# receiver.net
KiCad netlist of a schematic drawn in EAGLE
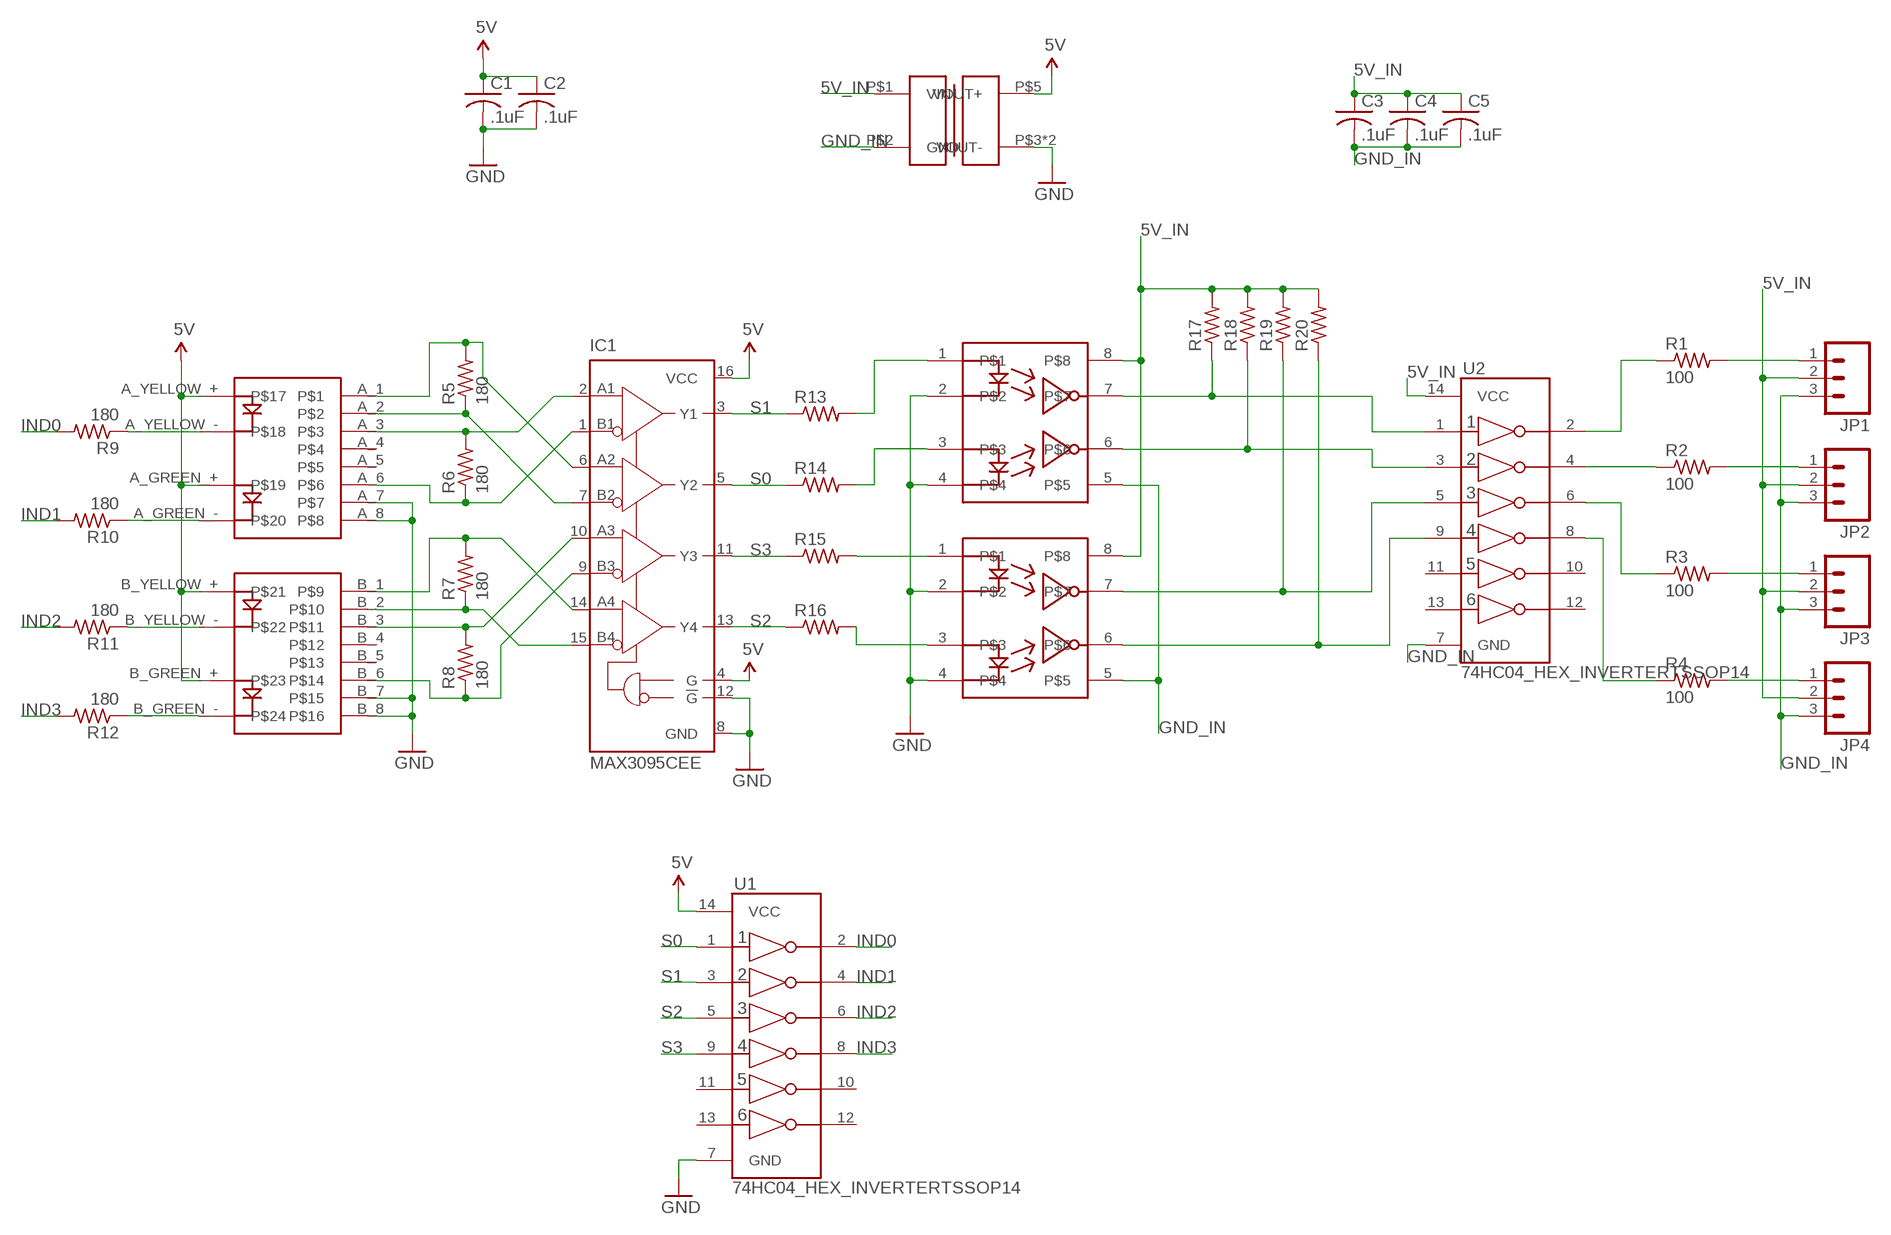
[diagram p0: schematic, sheet 1]

(export (version "E")
  (design (tool "Eeschema 10.0.6"))
  (components
    (comp (ref "C1")
      (value ".1uF")
      (footprint "eagle-import:C0603")
      (libsource (lib "eagle-import") (part "C-USC0603"))
    )
    (comp (ref "C2")
      (value ".1uF")
      (footprint "eagle-import:C0603")
      (libsource (lib "eagle-import") (part "C-USC0603"))
    )
    (comp (ref "C3")
      (value ".1uF")
      (footprint "eagle-import:C0603")
      (libsource (lib "eagle-import") (part "C-USC0603"))
    )
    (comp (ref "C4")
      (value ".1uF")
      (footprint "eagle-import:C0603")
      (libsource (lib "eagle-import") (part "C-USC0603"))
    )
    (comp (ref "C5")
      (value ".1uF")
      (footprint "eagle-import:C0603")
      (libsource (lib "eagle-import") (part "C-USC0603"))
    )
    (comp (ref "IC1")
      (value "MAX3095CEE")
      (footprint "eagle-import:QSOP16")
      (fields (field (name "MPN") "MAX3095CEE+"))
      (libsource (lib "eagle-import") (part "MAX309EE5C"))
    )
    (comp (ref "JP1")
      (value "M03-SCREW-5MM")
      (footprint "eagle-import:SCREWTERMINAL-5MM-3")
      (libsource (lib "eagle-import") (part "M03-SCREW-5MM"))
    )
    (comp (ref "JP2")
      (value "M03-SCREW-5MM")
      (footprint "eagle-import:SCREWTERMINAL-5MM-3")
      (libsource (lib "eagle-import") (part "M03-SCREW-5MM"))
    )
    (comp (ref "JP3")
      (value "M03-SCREW-5MM")
      (footprint "eagle-import:SCREWTERMINAL-5MM-3")
      (libsource (lib "eagle-import") (part "M03-SCREW-5MM"))
    )
    (comp (ref "JP4")
      (value "M03-SCREW-5MM")
      (footprint "eagle-import:SCREWTERMINAL-5MM-3")
      (libsource (lib "eagle-import") (part "M03-SCREW-5MM"))
    )
    (comp (ref "R1")
      (value "100")
      (footprint "eagle-import:R0603")
      (libsource (lib "eagle-import") (part "R-US_R0603"))
    )
    (comp (ref "R2")
      (value "100")
      (footprint "eagle-import:R0603")
      (libsource (lib "eagle-import") (part "R-US_R0603"))
    )
    (comp (ref "R3")
      (value "100")
      (footprint "eagle-import:R0603")
      (libsource (lib "eagle-import") (part "R-US_R0603"))
    )
    (comp (ref "R4")
      (value "100")
      (footprint "eagle-import:R0603")
      (libsource (lib "eagle-import") (part "R-US_R0603"))
    )
    (comp (ref "R5")
      (value "180")
      (footprint "eagle-import:R0603")
      (libsource (lib "eagle-import") (part "R-US_R0603"))
    )
    (comp (ref "R6")
      (value "180")
      (footprint "eagle-import:R0603")
      (libsource (lib "eagle-import") (part "R-US_R0603"))
    )
    (comp (ref "R7")
      (value "180")
      (footprint "eagle-import:R0603")
      (libsource (lib "eagle-import") (part "R-US_R0603"))
    )
    (comp (ref "R8")
      (value "180")
      (footprint "eagle-import:R0603")
      (libsource (lib "eagle-import") (part "R-US_R0603"))
    )
    (comp (ref "R9")
      (value "180")
      (footprint "eagle-import:R0603")
      (libsource (lib "eagle-import") (part "R-US_R0603"))
    )
    (comp (ref "R10")
      (value "180")
      (footprint "eagle-import:R0603")
      (libsource (lib "eagle-import") (part "R-US_R0603"))
    )
    (comp (ref "R11")
      (value "180")
      (footprint "eagle-import:R0603")
      (libsource (lib "eagle-import") (part "R-US_R0603"))
    )
    (comp (ref "R12")
      (value "180")
      (footprint "eagle-import:R0603")
      (libsource (lib "eagle-import") (part "R-US_R0603"))
    )
    (comp (ref "R13")
      (value "R-US_R0603")
      (footprint "eagle-import:R0603")
      (libsource (lib "eagle-import") (part "R-US_R0603"))
    )
    (comp (ref "R14")
      (value "R-US_R0603")
      (footprint "eagle-import:R0603")
      (libsource (lib "eagle-import") (part "R-US_R0603"))
    )
    (comp (ref "R15")
      (value "R-US_R0603")
      (footprint "eagle-import:R0603")
      (libsource (lib "eagle-import") (part "R-US_R0603"))
    )
    (comp (ref "R16")
      (value "R-US_R0603")
      (footprint "eagle-import:R0603")
      (libsource (lib "eagle-import") (part "R-US_R0603"))
    )
    (comp (ref "R17")
      (value "R-US_R0603")
      (footprint "eagle-import:R0603")
      (libsource (lib "eagle-import") (part "R-US_R0603"))
    )
    (comp (ref "R18")
      (value "R-US_R0603")
      (footprint "eagle-import:R0603")
      (libsource (lib "eagle-import") (part "R-US_R0603"))
    )
    (comp (ref "R19")
      (value "R-US_R0603")
      (footprint "eagle-import:R0603")
      (libsource (lib "eagle-import") (part "R-US_R0603"))
    )
    (comp (ref "R20")
      (value "R-US_R0603")
      (footprint "eagle-import:R0603")
      (libsource (lib "eagle-import") (part "R-US_R0603"))
    )
    (comp (ref "U$1")
      (value "RJ45_2X1")
      (footprint "eagle-import:RJ45_2X1")
      (libsource (lib "eagle-import") (part "RJ45_2X1"))
    )
    (comp (ref "U$2")
      (value "DC_DC_ISOLATED_0505")
      (footprint "eagle-import:IB_XLS-1W")
      (libsource (lib "eagle-import") (part "DC_DC_ISOLATED_0505"))
    )
    (comp (ref "U$3")
      (value "HCPL-0631-500E")
      (footprint "eagle-import:SO08")
      (libsource (lib "eagle-import") (part "HCPL-0631-500E"))
    )
    (comp (ref "U$4")
      (value "HCPL-0631-500E")
      (footprint "eagle-import:SO08")
      (libsource (lib "eagle-import") (part "HCPL-0631-500E"))
    )
    (comp (ref "U1")
      (value "74HC04_HEX_INVERTERTSSOP14")
      (footprint "eagle-import:TSSOP14")
      (libsource (lib "eagle-import") (part "74HC04_HEX_INVERTERTSSOP14"))
    )
    (comp (ref "U2")
      (value "74HC04_HEX_INVERTERTSSOP14")
      (footprint "eagle-import:TSSOP14")
      (libsource (lib "eagle-import") (part "74HC04_HEX_INVERTERTSSOP14"))
    )
  )
  (nets
    (net (code "1") (name "/5V_IN") (class "Default")
      (node (ref "C3") (pin "1") (pinfunction "1_1") (pintype "passive"))
      (node (ref "C4") (pin "1") (pinfunction "1_1") (pintype "passive"))
      (node (ref "C5") (pin "1") (pinfunction "1_1") (pintype "passive"))
      (node (ref "JP1") (pin "2") (pinfunction "2_2") (pintype "passive"))
      (node (ref "JP2") (pin "2") (pinfunction "2_2") (pintype "passive"))
      (node (ref "JP3") (pin "2") (pinfunction "2_2") (pintype "passive"))
      (node (ref "JP4") (pin "2") (pinfunction "2_2") (pintype "passive"))
      (node (ref "R17") (pin "2") (pinfunction "2_2") (pintype "passive"))
      (node (ref "R18") (pin "2") (pinfunction "2_2") (pintype "passive"))
      (node (ref "R19") (pin "2") (pinfunction "2_2") (pintype "passive"))
      (node (ref "R20") (pin "2") (pinfunction "2_2") (pintype "passive"))
      (node (ref "U$2") (pin "P$1") (pinfunction "VIN_P$1") (pintype "power_in"))
      (node (ref "U$3") (pin "8") (pinfunction "P$8_8") (pintype "bidirectional"))
      (node (ref "U$4") (pin "8") (pinfunction "P$8_8") (pintype "bidirectional"))
      (node (ref "U2") (pin "14") (pinfunction "VCC_14") (pintype "power_in"))
    )
    (net (code "2") (name "/GND_IN") (class "Default")
      (node (ref "C3") (pin "2") (pinfunction "2_2") (pintype "passive"))
      (node (ref "C4") (pin "2") (pinfunction "2_2") (pintype "passive"))
      (node (ref "C5") (pin "2") (pinfunction "2_2") (pintype "passive"))
      (node (ref "JP1") (pin "3") (pinfunction "3_3") (pintype "passive"))
      (node (ref "JP2") (pin "3") (pinfunction "3_3") (pintype "passive"))
      (node (ref "JP3") (pin "3") (pinfunction "3_3") (pintype "passive"))
      (node (ref "JP4") (pin "3") (pinfunction "3_3") (pintype "passive"))
      (node (ref "U$2") (pin "P$2") (pinfunction "GND_P$2") (pintype "power_in"))
      (node (ref "U$3") (pin "5") (pinfunction "P$5_5") (pintype "bidirectional"))
      (node (ref "U$4") (pin "5") (pinfunction "P$5_5") (pintype "bidirectional"))
      (node (ref "U2") (pin "7") (pinfunction "GND_7") (pintype "power_in"))
    )
    (net (code "3") (name "/IND0") (class "Default")
      (node (ref "R9") (pin "2") (pinfunction "2_2") (pintype "passive"))
      (node (ref "U1") (pin "2") (pinfunction "1Y_2") (pintype "output"))
    )
    (net (code "4") (name "/IND1") (class "Default")
      (node (ref "R10") (pin "2") (pinfunction "2_2") (pintype "passive"))
      (node (ref "U1") (pin "4") (pinfunction "2Y_4") (pintype "output"))
    )
    (net (code "5") (name "/IND2") (class "Default")
      (node (ref "R11") (pin "2") (pinfunction "2_2") (pintype "passive"))
      (node (ref "U1") (pin "6") (pinfunction "3Y_6") (pintype "output"))
    )
    (net (code "6") (name "/IND3") (class "Default")
      (node (ref "R12") (pin "2") (pinfunction "2_2") (pintype "passive"))
      (node (ref "U1") (pin "8") (pinfunction "4Y_8") (pintype "output"))
    )
    (net (code "7") (name "/S0") (class "Default")
      (node (ref "IC1") (pin "5") (pinfunction "Y2_5") (pintype "output"))
      (node (ref "R14") (pin "1") (pinfunction "1_1") (pintype "passive"))
      (node (ref "U1") (pin "1") (pinfunction "1A_1") (pintype "input"))
    )
    (net (code "8") (name "/S1") (class "Default")
      (node (ref "IC1") (pin "3") (pinfunction "Y1_3") (pintype "output"))
      (node (ref "R13") (pin "1") (pinfunction "1_1") (pintype "passive"))
      (node (ref "U1") (pin "3") (pinfunction "2A_3") (pintype "input"))
    )
    (net (code "9") (name "/S2") (class "Default")
      (node (ref "IC1") (pin "13") (pinfunction "Y4_13") (pintype "output"))
      (node (ref "R16") (pin "1") (pinfunction "1_1") (pintype "passive"))
      (node (ref "U1") (pin "5") (pinfunction "3A_5") (pintype "input"))
    )
    (net (code "10") (name "/S3") (class "Default")
      (node (ref "IC1") (pin "11") (pinfunction "Y3_11") (pintype "output"))
      (node (ref "R15") (pin "1") (pinfunction "1_1") (pintype "passive"))
      (node (ref "U1") (pin "9") (pinfunction "4A_9") (pintype "input"))
    )
    (net (code "11") (name "5V") (class "Default")
      (node (ref "C1") (pin "1") (pinfunction "1_1") (pintype "passive"))
      (node (ref "C2") (pin "1") (pinfunction "1_1") (pintype "passive"))
      (node (ref "IC1") (pin "16") (pinfunction "VCC_16") (pintype "output"))
      (node (ref "IC1") (pin "4") (pinfunction "G_4") (pintype "input"))
      (node (ref "U$1") (pin "A_GREEN_+") (pinfunction "P$19_A_GREEN_+") (pintype "bidirectional"))
      (node (ref "U$1") (pin "A_YELLOW_+") (pinfunction "P$17_A_YELLOW_+") (pintype "bidirectional"))
      (node (ref "U$1") (pin "B_GREEN_+") (pinfunction "P$23_B_GREEN_+") (pintype "bidirectional"))
      (node (ref "U$1") (pin "B_YELLOW_+") (pinfunction "P$21_B_YELLOW_+") (pintype "bidirectional"))
      (node (ref "U$2") (pin "P$5") (pinfunction "VOUT+_P$5") (pintype "power_in"))
      (node (ref "U1") (pin "14") (pinfunction "VCC_14") (pintype "power_in"))
    )
    (net (code "12") (name "GND") (class "Default")
      (node (ref "C1") (pin "2") (pinfunction "2_2") (pintype "passive"))
      (node (ref "C2") (pin "2") (pinfunction "2_2") (pintype "passive"))
      (node (ref "IC1") (pin "12") (pinfunction "~{G}_12") (pintype "input"))
      (node (ref "IC1") (pin "8") (pinfunction "GND_8") (pintype "power_in"))
      (node (ref "U$1") (pin "A_7") (pinfunction "P$7_A_7") (pintype "bidirectional"))
      (node (ref "U$1") (pin "A_8") (pinfunction "P$8_A_8") (pintype "bidirectional"))
      (node (ref "U$1") (pin "B_7") (pinfunction "P$15_B_7") (pintype "bidirectional"))
      (node (ref "U$1") (pin "B_8") (pinfunction "P$16_B_8") (pintype "bidirectional"))
      (node (ref "U$2") (pin "P$3") (pinfunction "VOUT-_P$3") (pintype "power_in"))
      (node (ref "U$2") (pin "P$4") (pinfunction "VOUT-_P$4") (pintype "power_in"))
      (node (ref "U$3") (pin "2") (pinfunction "P$2_2") (pintype "bidirectional"))
      (node (ref "U$3") (pin "4") (pinfunction "P$4_4") (pintype "bidirectional"))
      (node (ref "U$4") (pin "2") (pinfunction "P$2_2") (pintype "bidirectional"))
      (node (ref "U$4") (pin "4") (pinfunction "P$4_4") (pintype "bidirectional"))
      (node (ref "U1") (pin "7") (pinfunction "GND_7") (pintype "power_in"))
    )
    (net (code "13") (name "Net-(IC1-A1)") (class "Default")
      (node (ref "IC1") (pin "2") (pinfunction "A1_2") (pintype "output"))
      (node (ref "R6") (pin "2") (pinfunction "2_2") (pintype "passive"))
      (node (ref "U$1") (pin "A_3") (pinfunction "P$3_A_3") (pintype "bidirectional"))
    )
    (net (code "14") (name "Net-(IC1-A2)") (class "Default")
      (node (ref "IC1") (pin "6") (pinfunction "A2_6") (pintype "output"))
      (node (ref "R5") (pin "2") (pinfunction "2_2") (pintype "passive"))
      (node (ref "U$1") (pin "A_1") (pinfunction "P$1_A_1") (pintype "bidirectional"))
    )
    (net (code "15") (name "Net-(IC1-A3)") (class "Default")
      (node (ref "IC1") (pin "10") (pinfunction "A3_10") (pintype "output"))
      (node (ref "R8") (pin "2") (pinfunction "2_2") (pintype "passive"))
      (node (ref "U$1") (pin "B_3") (pinfunction "P$11_B_3") (pintype "bidirectional"))
    )
    (net (code "16") (name "Net-(IC1-A4)") (class "Default")
      (node (ref "IC1") (pin "14") (pinfunction "A4_14") (pintype "output"))
      (node (ref "R7") (pin "2") (pinfunction "2_2") (pintype "passive"))
      (node (ref "U$1") (pin "B_1") (pinfunction "P$9_B_1") (pintype "bidirectional"))
    )
    (net (code "17") (name "Net-(IC1-B1)") (class "Default")
      (node (ref "IC1") (pin "1") (pinfunction "B1_1") (pintype "output"))
      (node (ref "R6") (pin "1") (pinfunction "1_1") (pintype "passive"))
      (node (ref "U$1") (pin "A_6") (pinfunction "P$6_A_6") (pintype "bidirectional"))
    )
    (net (code "18") (name "Net-(IC1-B2)") (class "Default")
      (node (ref "IC1") (pin "7") (pinfunction "B2_7") (pintype "output"))
      (node (ref "R5") (pin "1") (pinfunction "1_1") (pintype "passive"))
      (node (ref "U$1") (pin "A_2") (pinfunction "P$2_A_2") (pintype "bidirectional"))
    )
    (net (code "19") (name "Net-(IC1-B3)") (class "Default")
      (node (ref "IC1") (pin "9") (pinfunction "B3_9") (pintype "output"))
      (node (ref "R8") (pin "1") (pinfunction "1_1") (pintype "passive"))
      (node (ref "U$1") (pin "B_6") (pinfunction "P$14_B_6") (pintype "bidirectional"))
    )
    (net (code "20") (name "Net-(IC1-B4)") (class "Default")
      (node (ref "IC1") (pin "15") (pinfunction "B4_15") (pintype "output"))
      (node (ref "R7") (pin "1") (pinfunction "1_1") (pintype "passive"))
      (node (ref "U$1") (pin "B_2") (pinfunction "P$10_B_2") (pintype "bidirectional"))
    )
    (net (code "21") (name "Net-(JP1-Pad1)") (class "Default")
      (node (ref "JP1") (pin "1") (pinfunction "1_1") (pintype "passive"))
      (node (ref "R1") (pin "2") (pinfunction "2_2") (pintype "passive"))
    )
    (net (code "22") (name "Net-(JP2-Pad1)") (class "Default")
      (node (ref "JP2") (pin "1") (pinfunction "1_1") (pintype "passive"))
      (node (ref "R2") (pin "2") (pinfunction "2_2") (pintype "passive"))
    )
    (net (code "23") (name "Net-(JP3-Pad1)") (class "Default")
      (node (ref "JP3") (pin "1") (pinfunction "1_1") (pintype "passive"))
      (node (ref "R3") (pin "2") (pinfunction "2_2") (pintype "passive"))
    )
    (net (code "24") (name "Net-(JP4-Pad1)") (class "Default")
      (node (ref "JP4") (pin "1") (pinfunction "1_1") (pintype "passive"))
      (node (ref "R4") (pin "2") (pinfunction "2_2") (pintype "passive"))
    )
    (net (code "25") (name "Net-(U$1-P$18)") (class "Default")
      (node (ref "R9") (pin "1") (pinfunction "1_1") (pintype "passive"))
      (node (ref "U$1") (pin "A_YELLOW_-") (pinfunction "P$18_A_YELLOW_-") (pintype "bidirectional"))
    )
    (net (code "26") (name "Net-(U$1-P$20)") (class "Default")
      (node (ref "R10") (pin "1") (pinfunction "1_1") (pintype "passive"))
      (node (ref "U$1") (pin "A_GREEN_-") (pinfunction "P$20_A_GREEN_-") (pintype "bidirectional"))
    )
    (net (code "27") (name "Net-(U$1-P$22)") (class "Default")
      (node (ref "R11") (pin "1") (pinfunction "1_1") (pintype "passive"))
      (node (ref "U$1") (pin "B_YELLOW_-") (pinfunction "P$22_B_YELLOW_-") (pintype "bidirectional"))
    )
    (net (code "28") (name "Net-(U$1-P$24)") (class "Default")
      (node (ref "R12") (pin "1") (pinfunction "1_1") (pintype "passive"))
      (node (ref "U$1") (pin "B_GREEN_-") (pinfunction "P$24_B_GREEN_-") (pintype "bidirectional"))
    )
    (net (code "29") (name "Net-(U$3-P$1)") (class "Default")
      (node (ref "R13") (pin "2") (pinfunction "2_2") (pintype "passive"))
      (node (ref "U$3") (pin "1") (pinfunction "P$1_1") (pintype "bidirectional"))
    )
    (net (code "30") (name "Net-(U$3-P$3)") (class "Default")
      (node (ref "R14") (pin "2") (pinfunction "2_2") (pintype "passive"))
      (node (ref "U$3") (pin "3") (pinfunction "P$3_3") (pintype "bidirectional"))
    )
    (net (code "31") (name "Net-(U$3-P$6)") (class "Default")
      (node (ref "R18") (pin "1") (pinfunction "1_1") (pintype "passive"))
      (node (ref "U$3") (pin "6") (pinfunction "P$6_6") (pintype "bidirectional"))
      (node (ref "U2") (pin "3") (pinfunction "2A_3") (pintype "input"))
    )
    (net (code "32") (name "Net-(U$3-P$7)") (class "Default")
      (node (ref "R17") (pin "1") (pinfunction "1_1") (pintype "passive"))
      (node (ref "U$3") (pin "7") (pinfunction "P$7_7") (pintype "bidirectional"))
      (node (ref "U2") (pin "1") (pinfunction "1A_1") (pintype "input"))
    )
    (net (code "33") (name "Net-(U$4-P$1)") (class "Default")
      (node (ref "R15") (pin "2") (pinfunction "2_2") (pintype "passive"))
      (node (ref "U$4") (pin "1") (pinfunction "P$1_1") (pintype "bidirectional"))
    )
    (net (code "34") (name "Net-(U$4-P$3)") (class "Default")
      (node (ref "R16") (pin "2") (pinfunction "2_2") (pintype "passive"))
      (node (ref "U$4") (pin "3") (pinfunction "P$3_3") (pintype "bidirectional"))
    )
    (net (code "35") (name "Net-(U$4-P$6)") (class "Default")
      (node (ref "R20") (pin "1") (pinfunction "1_1") (pintype "passive"))
      (node (ref "U$4") (pin "6") (pinfunction "P$6_6") (pintype "bidirectional"))
      (node (ref "U2") (pin "9") (pinfunction "4A_9") (pintype "input"))
    )
    (net (code "36") (name "Net-(U$4-P$7)") (class "Default")
      (node (ref "R19") (pin "1") (pinfunction "1_1") (pintype "passive"))
      (node (ref "U$4") (pin "7") (pinfunction "P$7_7") (pintype "bidirectional"))
      (node (ref "U2") (pin "5") (pinfunction "3A_5") (pintype "input"))
    )
    (net (code "37") (name "Net-(U2-1Y)") (class "Default")
      (node (ref "R1") (pin "1") (pinfunction "1_1") (pintype "passive"))
      (node (ref "U2") (pin "2") (pinfunction "1Y_2") (pintype "output"))
    )
    (net (code "38") (name "Net-(U2-2Y)") (class "Default")
      (node (ref "R2") (pin "1") (pinfunction "1_1") (pintype "passive"))
      (node (ref "U2") (pin "4") (pinfunction "2Y_4") (pintype "output"))
    )
    (net (code "39") (name "Net-(U2-3Y)") (class "Default")
      (node (ref "R3") (pin "1") (pinfunction "1_1") (pintype "passive"))
      (node (ref "U2") (pin "6") (pinfunction "3Y_6") (pintype "output"))
    )
    (net (code "40") (name "Net-(U2-4Y)") (class "Default")
      (node (ref "R4") (pin "1") (pinfunction "1_1") (pintype "passive"))
      (node (ref "U2") (pin "8") (pinfunction "4Y_8") (pintype "output"))
    )
    (net (code "41") (name "unconnected-(U$1-P$4-PadA_4)") (class "Default")
      (node (ref "U$1") (pin "A_4") (pinfunction "P$4_A_4") (pintype "bidirectional"))
    )
    (net (code "42") (name "unconnected-(U$1-P$5-PadA_5)") (class "Default")
      (node (ref "U$1") (pin "A_5") (pinfunction "P$5_A_5") (pintype "bidirectional"))
    )
    (net (code "43") (name "unconnected-(U$1-P$12-PadB_4)") (class "Default")
      (node (ref "U$1") (pin "B_4") (pinfunction "P$12_B_4") (pintype "bidirectional"))
    )
    (net (code "44") (name "unconnected-(U$1-P$13-PadB_5)") (class "Default")
      (node (ref "U$1") (pin "B_5") (pinfunction "P$13_B_5") (pintype "bidirectional"))
    )
    (net (code "45") (name "unconnected-(U1-5A-Pad11)") (class "Default")
      (node (ref "U1") (pin "11") (pinfunction "5A_11") (pintype "input"))
    )
    (net (code "46") (name "unconnected-(U1-5Y-Pad10)") (class "Default")
      (node (ref "U1") (pin "10") (pinfunction "5Y_10") (pintype "output"))
    )
    (net (code "47") (name "unconnected-(U1-6A-Pad13)") (class "Default")
      (node (ref "U1") (pin "13") (pinfunction "6A_13") (pintype "input"))
    )
    (net (code "48") (name "unconnected-(U1-6Y-Pad12)") (class "Default")
      (node (ref "U1") (pin "12") (pinfunction "6Y_12") (pintype "output"))
    )
    (net (code "49") (name "unconnected-(U2-5A-Pad11)") (class "Default")
      (node (ref "U2") (pin "11") (pinfunction "5A_11") (pintype "input"))
    )
    (net (code "50") (name "unconnected-(U2-5Y-Pad10)") (class "Default")
      (node (ref "U2") (pin "10") (pinfunction "5Y_10") (pintype "output"))
    )
    (net (code "51") (name "unconnected-(U2-6A-Pad13)") (class "Default")
      (node (ref "U2") (pin "13") (pinfunction "6A_13") (pintype "input"))
    )
    (net (code "52") (name "unconnected-(U2-6Y-Pad12)") (class "Default")
      (node (ref "U2") (pin "12") (pinfunction "6Y_12") (pintype "output"))
    )
  )
)
